# Temp_Sensor.net
KiCad netlist of a schematic drawn in Altium Designer
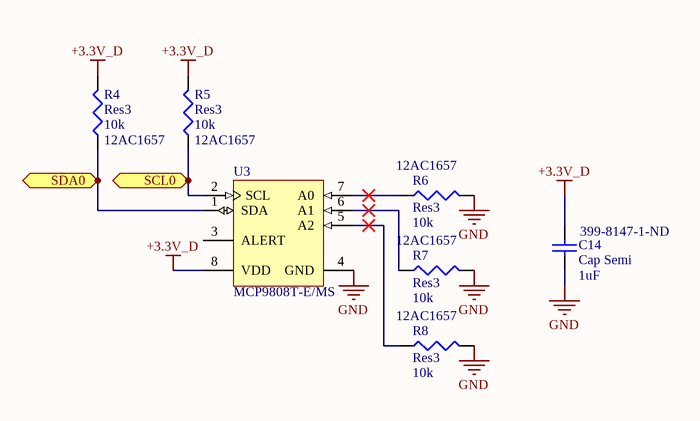
[diagram p0: Temp_Sensor.SchDoc]

(export (version "E")
  (design (tool "Eeschema 10.0.6"))
  (components
    (comp (ref "C14")
      (value "Cap Semi")
      (footprint "C1206")
      (description "Multilayer Ceramic Capacitors MLCC - SMD/SMT 50volts 1uF X7R 10%")
      (fields
        (field (name "ALTIUM_VALUE") "1uF")
        (field (name "SUPPLIER PART NUMBER 1") "399-8147-1-ND")
        (field (name "MANUFACTURER") "KEMET")
        (field (name "MANUFACTURER PART NUMBER") "C1206C105K5RACTU")
        (field (name "PUBLISHER") "Altium Limited")
      )
      (libsource (lib "Miscellaneous Devices") (part "Cap Semi"))
    )
    (comp (ref "R4")
      (value "Res3")
      (footprint "6-0805_L")
      (description "VISHAY BC COMPONENTS   MCT06030C1002FP500   RESISTOR, 0603, 10KOHM, 100mW, 1PER")
      (fields
        (field (name "ALTIUM_VALUE") "10k")
        (field (name "SUPPLIER PART NUMBER 1") "12AC1657")
        (field (name "MANUFACTURER") "Vishay")
        (field (name "MANUFACTURER PART NUMBER") "MCT06030C1002FP500")
        (field (name "PUBLISHER") "Altium Limited")
      )
      (libsource (lib "Miscellaneous Devices") (part "Res3"))
    )
    (comp (ref "R5")
      (value "Res3")
      (footprint "6-0805_L")
      (description "VISHAY BC COMPONENTS   MCT06030C1002FP500   RESISTOR, 0603, 10KOHM, 100mW, 1PER")
      (fields
        (field (name "ALTIUM_VALUE") "10k")
        (field (name "SUPPLIER PART NUMBER 1") "12AC1657")
        (field (name "MANUFACTURER") "Vishay")
        (field (name "MANUFACTURER PART NUMBER") "MCT06030C1002FP500")
        (field (name "PUBLISHER") "Altium Limited")
      )
      (libsource (lib "Miscellaneous Devices") (part "Res3"))
    )
    (comp (ref "R6")
      (value "Res3")
      (footprint "6-0805_L")
      (description "VISHAY BC COMPONENTS   MCT06030C1002FP500   RESISTOR, 0603, 10KOHM, 100mW, 1PER")
      (fields
        (field (name "ALTIUM_VALUE") "10k")
        (field (name "SUPPLIER PART NUMBER 1") "12AC1657")
        (field (name "MANUFACTURER") "Vishay")
        (field (name "MANUFACTURER PART NUMBER") "MCT06030C1002FP500")
        (field (name "PUBLISHER") "Altium Limited")
      )
      (libsource (lib "Miscellaneous Devices") (part "Res3"))
    )
    (comp (ref "R7")
      (value "Res3")
      (footprint "6-0805_L")
      (description "VISHAY BC COMPONENTS   MCT06030C1002FP500   RESISTOR, 0603, 10KOHM, 100mW, 1PER")
      (fields
        (field (name "ALTIUM_VALUE") "10k")
        (field (name "SUPPLIER PART NUMBER 1") "12AC1657")
        (field (name "MANUFACTURER") "Vishay")
        (field (name "MANUFACTURER PART NUMBER") "MCT06030C1002FP500")
        (field (name "PUBLISHER") "Altium Limited")
      )
      (libsource (lib "Miscellaneous Devices") (part "Res3"))
    )
    (comp (ref "R8")
      (value "Res3")
      (footprint "6-0805_L")
      (description "VISHAY BC COMPONENTS   MCT06030C1002FP500   RESISTOR, 0603, 10KOHM, 100mW, 1PER")
      (fields
        (field (name "ALTIUM_VALUE") "10k")
        (field (name "SUPPLIER PART NUMBER 1") "12AC1657")
        (field (name "MANUFACTURER") "Vishay")
        (field (name "MANUFACTURER PART NUMBER") "MCT06030C1002FP500")
        (field (name "PUBLISHER") "Altium Limited")
      )
      (libsource (lib "Miscellaneous Devices") (part "Res3"))
    )
    (comp (ref "U3")
      (value "MCP9808T-E/MS")
      (footprint "MCHP-MSOP-MS8_M")
      (fields (field (name "MANUFACTURER") "Microchip"))
      (libsource (lib "Altium Content Vault") (part "MCHP-MCP9808-MSOP-8"))
    )
  )
  (nets
    (net (code "1") (name "+3.3V_D") (class "Default")
      (node (ref "C14") (pin "2") (pinfunction "2_2") (pintype "passive"))
      (node (ref "R4") (pin "2") (pinfunction "2_2") (pintype "passive"))
      (node (ref "R5") (pin "2") (pinfunction "2_2") (pintype "passive"))
      (node (ref "U3") (pin "8") (pinfunction "VDD_8") (pintype "power_in"))
    )
    (net (code "2") (name "/SCL0") (class "Default")
      (node (ref "R5") (pin "1") (pinfunction "1_1") (pintype "passive"))
      (node (ref "U3") (pin "2") (pinfunction "SCL_2") (pintype "input"))
    )
    (net (code "3") (name "/SDA0") (class "Default")
      (node (ref "R4") (pin "1") (pinfunction "1_1") (pintype "passive"))
      (node (ref "U3") (pin "1") (pinfunction "SDA_1") (pintype "bidirectional"))
    )
    (net (code "4") (name "GND") (class "Default")
      (node (ref "C14") (pin "1") (pinfunction "1_1") (pintype "passive"))
      (node (ref "R6") (pin "2") (pinfunction "2_2") (pintype "passive"))
      (node (ref "R7") (pin "2") (pinfunction "2_2") (pintype "passive"))
      (node (ref "R8") (pin "2") (pinfunction "2_2") (pintype "passive"))
      (node (ref "U3") (pin "4") (pinfunction "GND_4") (pintype "power_in"))
    )
    (net (code "5") (name "Net-(U3-A0)") (class "Default")
      (node (ref "R6") (pin "1") (pinfunction "1_1") (pintype "passive"))
      (node (ref "U3") (pin "7") (pinfunction "A0_7") (pintype "input"))
    )
    (net (code "6") (name "Net-(U3-A1)") (class "Default")
      (node (ref "R7") (pin "1") (pinfunction "1_1") (pintype "passive"))
      (node (ref "U3") (pin "6") (pinfunction "A1_6") (pintype "input"))
    )
    (net (code "7") (name "Net-(U3-A2)") (class "Default")
      (node (ref "R8") (pin "1") (pinfunction "1_1") (pintype "passive"))
      (node (ref "U3") (pin "5") (pinfunction "A2_5") (pintype "input"))
    )
    (net (code "8") (name "unconnected-(U3-ALERT-Pad3)") (class "Default")
      (node (ref "U3") (pin "3") (pinfunction "ALERT_3") (pintype "open_collector"))
    )
  )
)
